# MCU.net
KiCad netlist of a schematic drawn in EAGLE
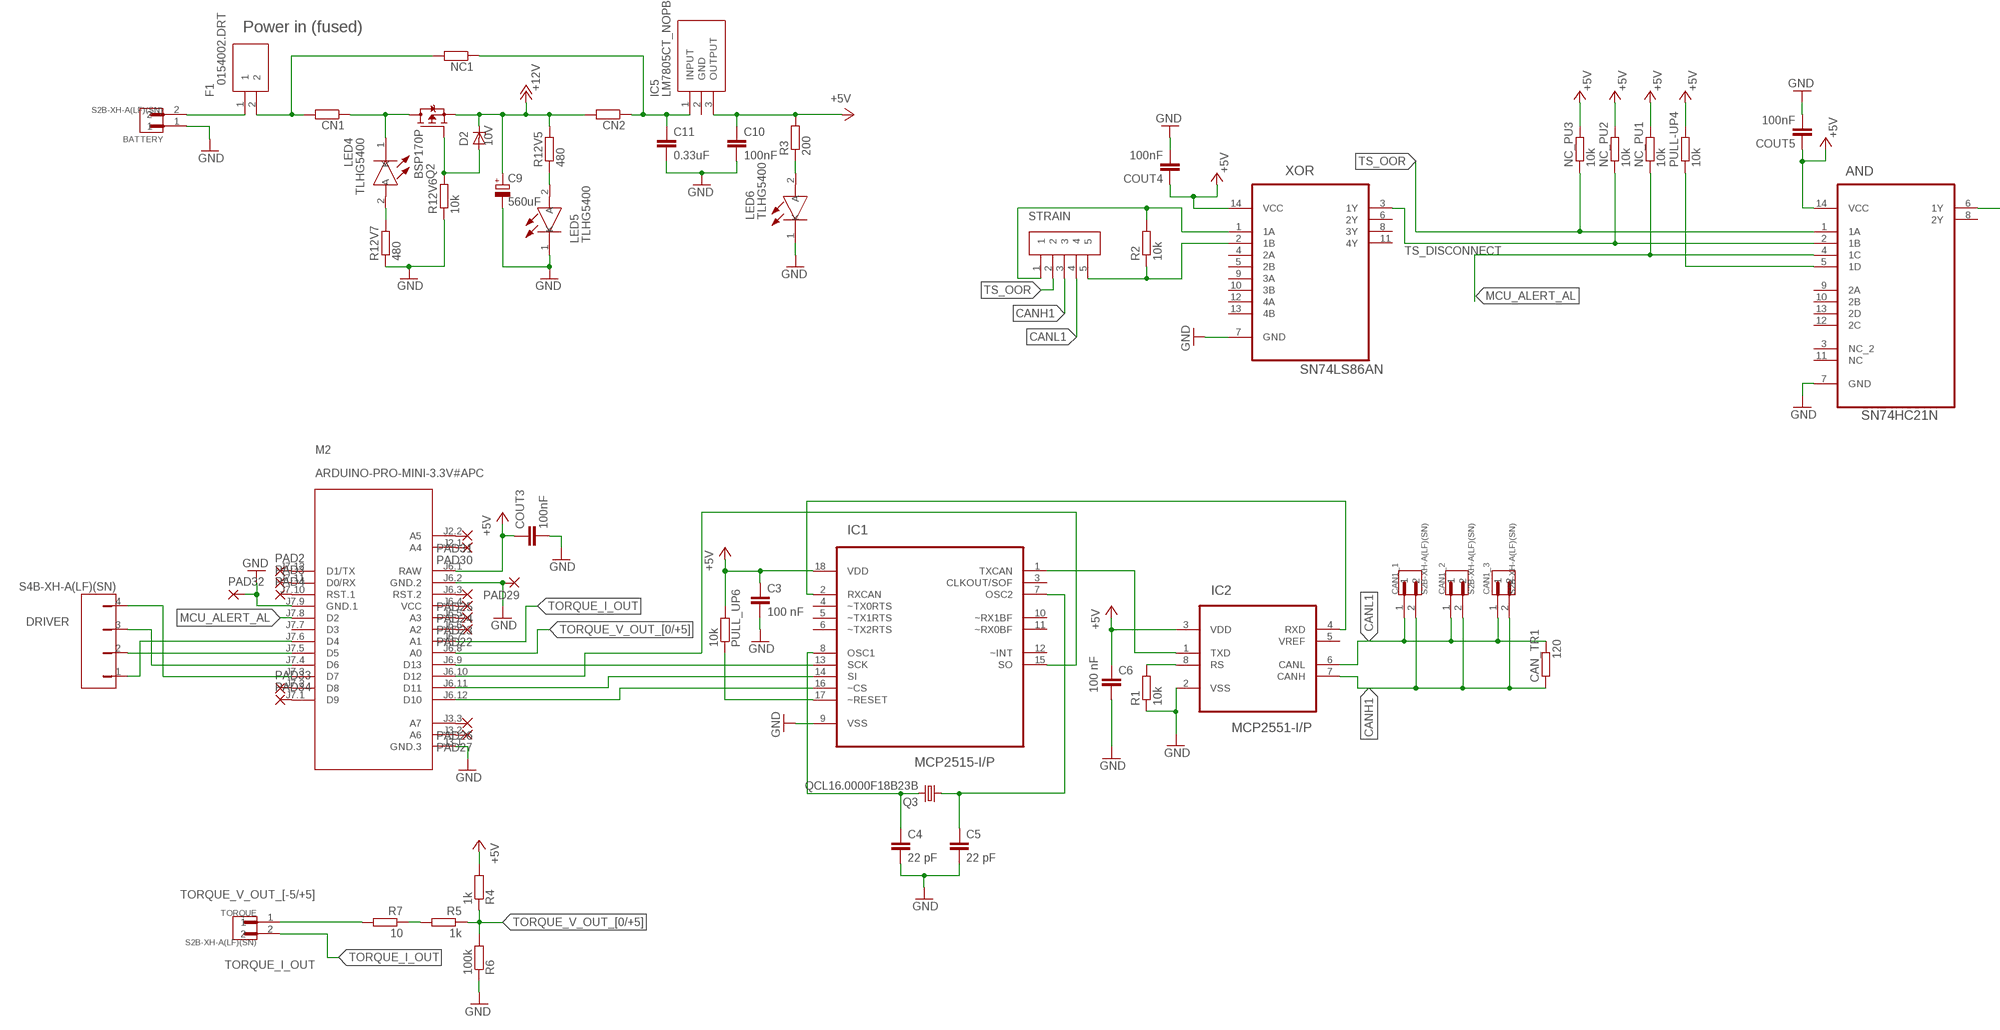
[diagram p0: schematic, sheet 1, part 1 of 2]
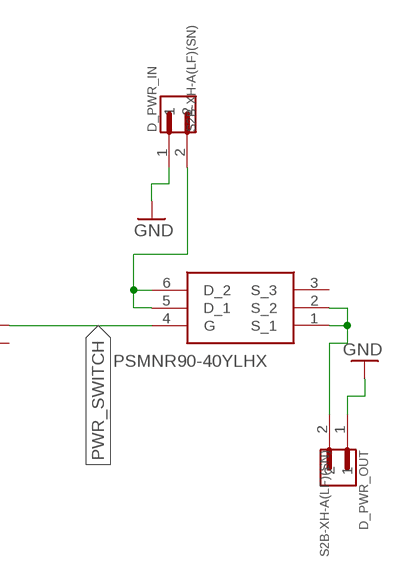
[diagram p1: schematic, sheet 1, part 2 of 2]
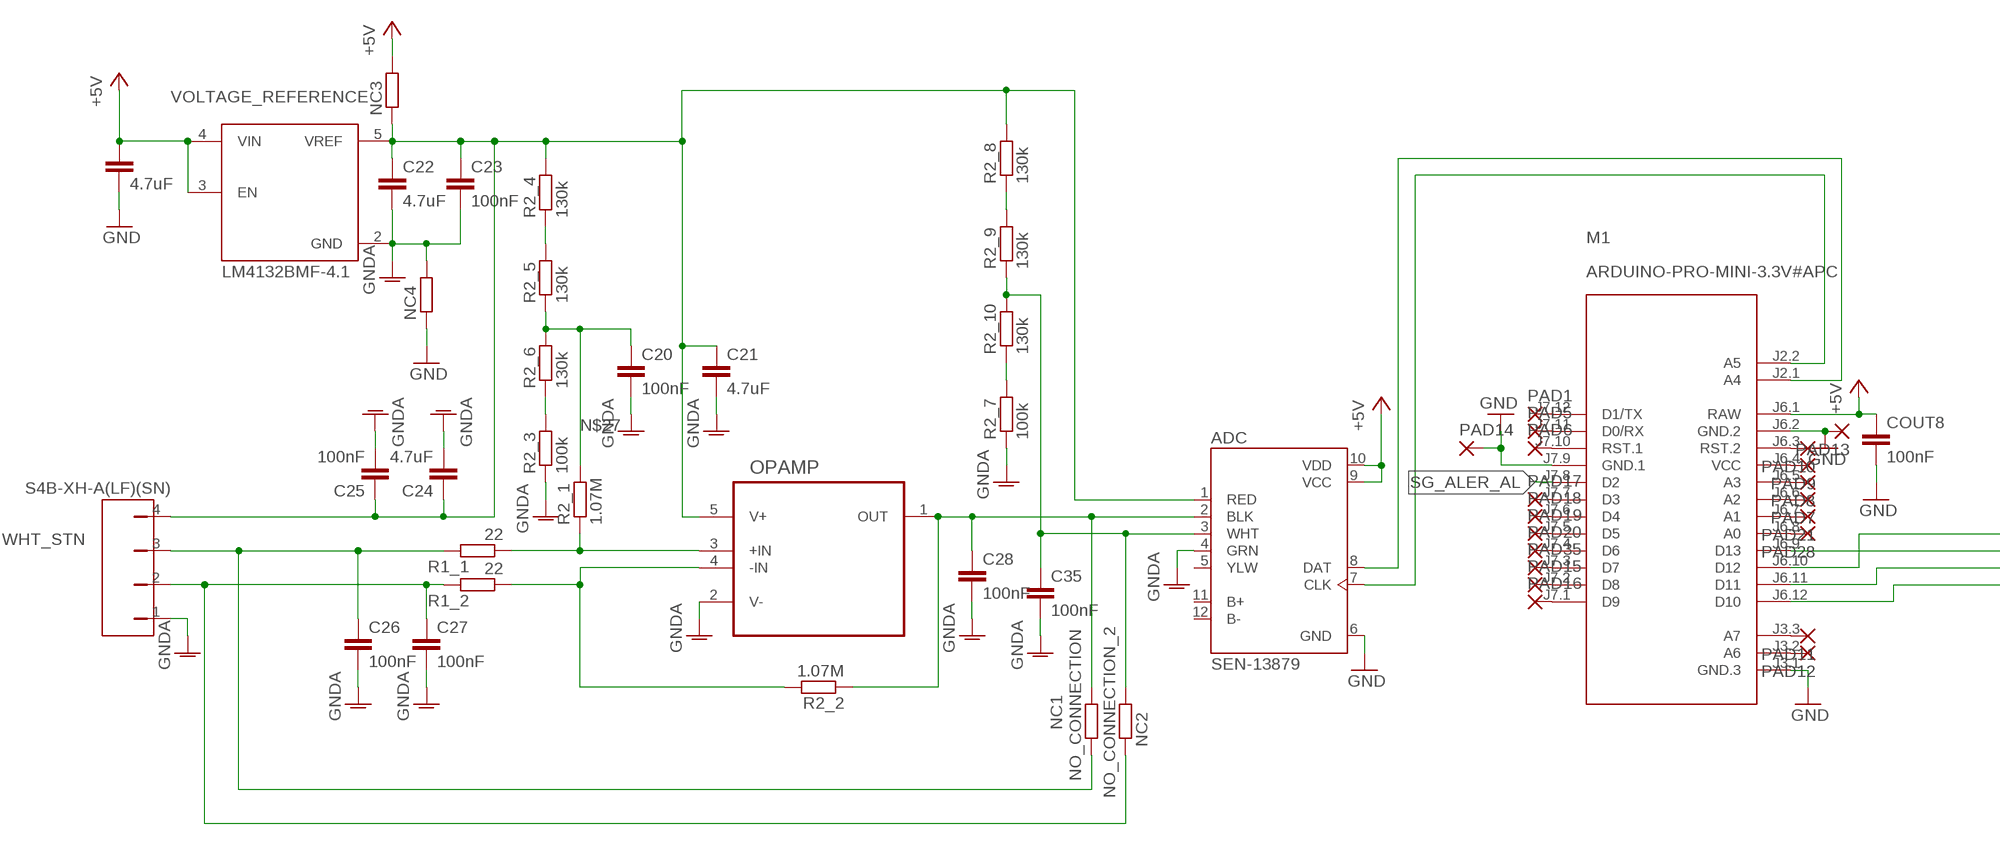
[diagram p2: schematic, sheet 2, part 1 of 2]
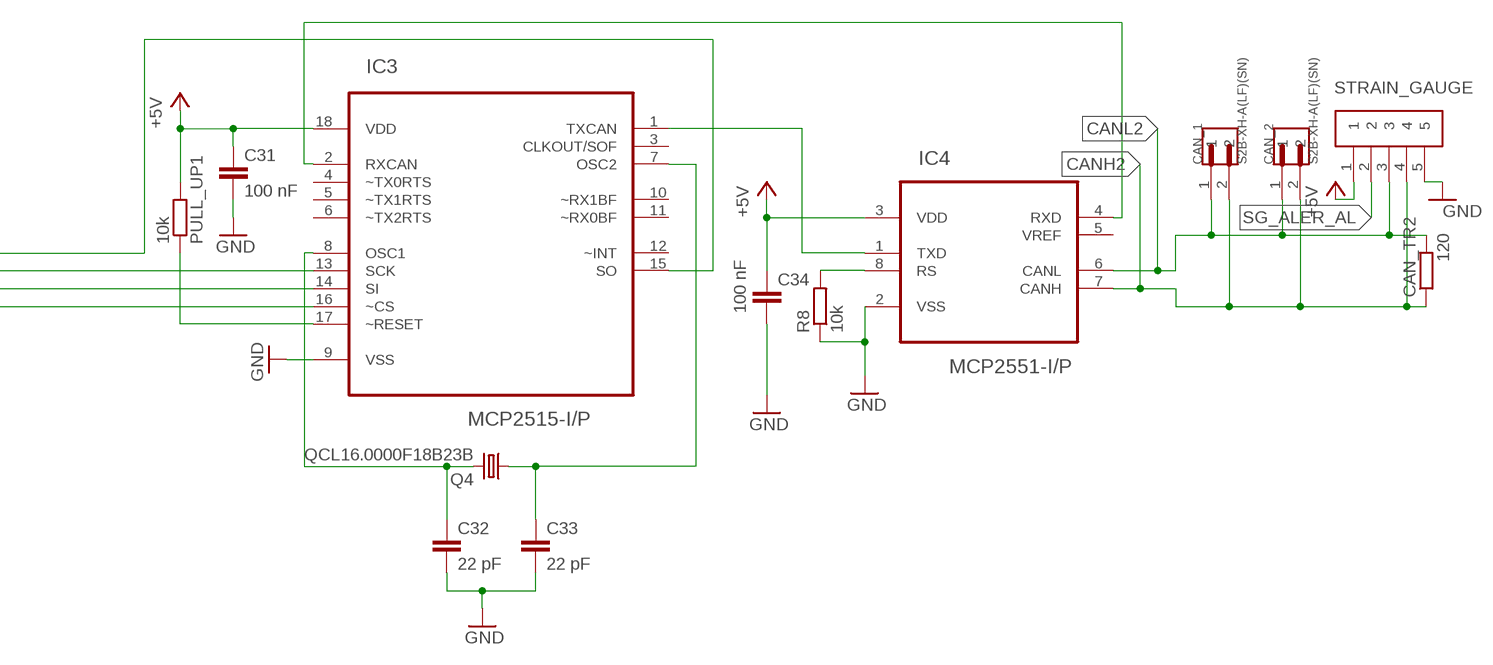
[diagram p3: schematic, sheet 2, part 2 of 2]

(export (version "E")
  (design (tool "Eeschema 10.0.6"))
  (components
    (comp (ref "ADC")
      (value "SEN-13879")
      (footprint "eagle-import:SPARKFUN_SEN-13879")
      (fields (field (name "DIGI-KEY_PART_NUMBER") "1568-1436-ND") (field (name "MF") "SparkFun"))
      (libsource (lib "eagle-import") (part "SEN-13879"))
    )
    (comp (ref "C19")
      (value "4.7uF")
      (footprint "eagle-import:C0805")
      (libsource (lib "eagle-import") (part "C-EUC0805"))
    )
    (comp (ref "C20")
      (value "100nF")
      (footprint "eagle-import:C0805")
      (libsource (lib "eagle-import") (part "C-EUC0805"))
    )
    (comp (ref "C21")
      (value "4.7uF")
      (footprint "eagle-import:C0805")
      (libsource (lib "eagle-import") (part "C-EUC0805"))
    )
    (comp (ref "C22")
      (value "4.7uF")
      (footprint "eagle-import:C0805")
      (libsource (lib "eagle-import") (part "C-EUC0805"))
    )
    (comp (ref "C23")
      (value "100nF")
      (footprint "eagle-import:C0805")
      (libsource (lib "eagle-import") (part "C-EUC0805"))
    )
    (comp (ref "C24")
      (value "4.7uF")
      (footprint "eagle-import:C0805")
      (libsource (lib "eagle-import") (part "C-EUC0805"))
    )
    (comp (ref "C25")
      (value "100nF")
      (footprint "eagle-import:C0805")
      (libsource (lib "eagle-import") (part "C-EUC0805"))
    )
    (comp (ref "C26")
      (value "100nF")
      (footprint "eagle-import:C0805")
      (libsource (lib "eagle-import") (part "C-EUC0805"))
    )
    (comp (ref "C27")
      (value "100nF")
      (footprint "eagle-import:C0805")
      (libsource (lib "eagle-import") (part "C-EUC0805"))
    )
    (comp (ref "C28")
      (value "100nF")
      (footprint "eagle-import:C0805")
      (libsource (lib "eagle-import") (part "C-EUC0805"))
    )
    (comp (ref "C31")
      (value "100 nF")
      (footprint "eagle-import:C0805")
      (libsource (lib "eagle-import") (part "C-EUC0805"))
    )
    (comp (ref "C32")
      (value "22 pF")
      (footprint "eagle-import:C0805")
      (libsource (lib "eagle-import") (part "C-EUC0805"))
    )
    (comp (ref "C33")
      (value "22 pF")
      (footprint "eagle-import:C0805")
      (libsource (lib "eagle-import") (part "C-EUC0805"))
    )
    (comp (ref "C34")
      (value "100 nF")
      (footprint "eagle-import:C0805")
      (libsource (lib "eagle-import") (part "C-EUC0805"))
    )
    (comp (ref "C35")
      (value "100nF")
      (footprint "eagle-import:C0805")
      (libsource (lib "eagle-import") (part "C-EUC0805"))
    )
    (comp (ref "CAN_1")
      (value "S2B-XH-A(LF)(SN)")
      (footprint "eagle-import:JST_S2B-XH-A(LF)(SN)")
      (fields
        (field (name "DIGI-KEY_PART_NUMBER") "455-2257-ND")
        (field (name "MF") "JST Sales")
        (field (name "MP") "S2B-XH-A_LF__SN_")
      )
      (libsource (lib "eagle-import") (part "S2B-XH-A(LF)(SN)"))
    )
    (comp (ref "CAN_2")
      (value "S2B-XH-A(LF)(SN)")
      (footprint "eagle-import:JST_S2B-XH-A(LF)(SN)")
      (fields
        (field (name "DIGI-KEY_PART_NUMBER") "455-2257-ND")
        (field (name "MF") "JST Sales")
        (field (name "MP") "S2B-XH-A_LF__SN_")
      )
      (libsource (lib "eagle-import") (part "S2B-XH-A(LF)(SN)"))
    )
    (comp (ref "CAN_TR2")
      (value "120")
      (footprint "eagle-import:R0805")
      (libsource (lib "eagle-import") (part "R-EU_R0805"))
    )
    (comp (ref "COUT8")
      (value "100nF")
      (footprint "eagle-import:C0805")
      (libsource (lib "eagle-import") (part "C-EUC0805"))
    )
    (comp (ref "IC3")
      (value "MCP2515-I/P")
      (footprint "eagle-import:DIP254P762X432-18")
      (fields (field (name "MF") "Microchip"))
      (libsource (lib "eagle-import") (part "MCP2515-I/P"))
    )
    (comp (ref "IC4")
      (value "MCP2551-I/P")
      (footprint "eagle-import:DIP254P762X432-8")
      (fields (field (name "MF") "Microchip"))
      (libsource (lib "eagle-import") (part "MCP2551-I/P"))
    )
    (comp (ref "M1")
      (value "ARDUINO-PRO-MINI-3.3V#APC")
      (footprint "eagle-import:ARDUINO-PRO-MINI#APC")
      (libsource (lib "eagle-import") (part "ARDUINO-PRO-MINI-#APC3.3V"))
    )
    (comp (ref "NC3")
      (value "R-EU_R0805")
      (footprint "eagle-import:R0805")
      (libsource (lib "eagle-import") (part "R-EU_R0805"))
    )
    (comp (ref "NC4")
      (value "R-EU_R0805")
      (footprint "eagle-import:R0805")
      (libsource (lib "eagle-import") (part "R-EU_R0805"))
    )
    (comp (ref "NO_CONNECTION")
      (value "NC1")
      (footprint "eagle-import:R0805")
      (libsource (lib "eagle-import") (part "R-EU_R0805"))
    )
    (comp (ref "NO_CONNECTION_2")
      (value "NC2")
      (footprint "eagle-import:R0805")
      (libsource (lib "eagle-import") (part "R-EU_R0805"))
    )
    (comp (ref "OPAMP")
      (value "LMP7731MF")
      (footprint "eagle-import:SOT95P284X119-5N")
      (fields (field (name "MF") "Texas Instruments"))
      (libsource (lib "eagle-import") (part "LMP7731MF"))
    )
    (comp (ref "PAD1")
      (value "SMD2")
      (footprint "eagle-import:SMD1,27-2,54")
      (libsource (lib "eagle-import") (part "SMD2"))
    )
    (comp (ref "PAD5")
      (value "SMD2")
      (footprint "eagle-import:SMD1,27-2,54")
      (libsource (lib "eagle-import") (part "SMD2"))
    )
    (comp (ref "PAD6")
      (value "SMD2")
      (footprint "eagle-import:SMD1,27-2,54")
      (libsource (lib "eagle-import") (part "SMD2"))
    )
    (comp (ref "PAD7")
      (value "SMD2")
      (footprint "eagle-import:SMD1,27-2,54")
      (libsource (lib "eagle-import") (part "SMD2"))
    )
    (comp (ref "PAD8")
      (value "SMD2")
      (footprint "eagle-import:SMD1,27-2,54")
      (libsource (lib "eagle-import") (part "SMD2"))
    )
    (comp (ref "PAD9")
      (value "SMD2")
      (footprint "eagle-import:SMD1,27-2,54")
      (libsource (lib "eagle-import") (part "SMD2"))
    )
    (comp (ref "PAD10")
      (value "SMD2")
      (footprint "eagle-import:SMD1,27-2,54")
      (libsource (lib "eagle-import") (part "SMD2"))
    )
    (comp (ref "PAD11")
      (value "SMD2")
      (footprint "eagle-import:SMD1,27-2,54")
      (libsource (lib "eagle-import") (part "SMD2"))
    )
    (comp (ref "PAD12")
      (value "SMD2")
      (footprint "eagle-import:SMD1,27-2,54")
      (libsource (lib "eagle-import") (part "SMD2"))
    )
    (comp (ref "PAD13")
      (value "SMD2")
      (footprint "eagle-import:SMD1,27-2,54")
      (libsource (lib "eagle-import") (part "SMD2"))
    )
    (comp (ref "PAD14")
      (value "SMD2")
      (footprint "eagle-import:SMD1,27-2,54")
      (libsource (lib "eagle-import") (part "SMD2"))
    )
    (comp (ref "PAD15")
      (value "SMD2")
      (footprint "eagle-import:SMD1,27-2,54")
      (libsource (lib "eagle-import") (part "SMD2"))
    )
    (comp (ref "PAD16")
      (value "SMD2")
      (footprint "eagle-import:SMD1,27-2,54")
      (libsource (lib "eagle-import") (part "SMD2"))
    )
    (comp (ref "PAD17")
      (value "SMD2")
      (footprint "eagle-import:SMD1,27-2,54")
      (libsource (lib "eagle-import") (part "SMD2"))
    )
    (comp (ref "PAD18")
      (value "SMD2")
      (footprint "eagle-import:SMD1,27-2,54")
      (libsource (lib "eagle-import") (part "SMD2"))
    )
    (comp (ref "PAD19")
      (value "SMD2")
      (footprint "eagle-import:SMD1,27-2,54")
      (libsource (lib "eagle-import") (part "SMD2"))
    )
    (comp (ref "PAD20")
      (value "SMD2")
      (footprint "eagle-import:SMD1,27-2,54")
      (libsource (lib "eagle-import") (part "SMD2"))
    )
    (comp (ref "PAD21")
      (value "SMD2")
      (footprint "eagle-import:SMD1,27-2,54")
      (libsource (lib "eagle-import") (part "SMD2"))
    )
    (comp (ref "PAD28")
      (value "SMD2")
      (footprint "eagle-import:SMD1,27-2,54")
      (libsource (lib "eagle-import") (part "SMD2"))
    )
    (comp (ref "PAD35")
      (value "SMD2")
      (footprint "eagle-import:SMD1,27-2,54")
      (libsource (lib "eagle-import") (part "SMD2"))
    )
    (comp (ref "PULL_UP1")
      (value "10k")
      (footprint "eagle-import:R0805")
      (libsource (lib "eagle-import") (part "R-EU_R0805"))
    )
    (comp (ref "Q4")
      (value "QCL16.0000F18B23B")
      (footprint "eagle-import:HC49_S")
      (libsource (lib "eagle-import") (part "CRYSTALHC49S"))
    )
    (comp (ref "R1_1")
      (value "22")
      (footprint "eagle-import:R0805")
      (libsource (lib "eagle-import") (part "R-EU_R0805"))
    )
    (comp (ref "R1_2")
      (value "22")
      (footprint "eagle-import:R0805")
      (libsource (lib "eagle-import") (part "R-EU_R0805"))
    )
    (comp (ref "R2_1")
      (value "1.07M")
      (footprint "eagle-import:R0805")
      (libsource (lib "eagle-import") (part "R-EU_R0805"))
    )
    (comp (ref "R2_2")
      (value "1.07M")
      (footprint "eagle-import:R0805")
      (libsource (lib "eagle-import") (part "R-EU_R0805"))
    )
    (comp (ref "R2_3")
      (value "100k")
      (footprint "eagle-import:R0805")
      (libsource (lib "eagle-import") (part "R-EU_R0805"))
    )
    (comp (ref "R2_4")
      (value "130k")
      (footprint "eagle-import:R0805")
      (libsource (lib "eagle-import") (part "R-EU_R0805"))
    )
    (comp (ref "R2_5")
      (value "130k")
      (footprint "eagle-import:R0805")
      (libsource (lib "eagle-import") (part "R-EU_R0805"))
    )
    (comp (ref "R2_6")
      (value "130k")
      (footprint "eagle-import:R0805")
      (libsource (lib "eagle-import") (part "R-EU_R0805"))
    )
    (comp (ref "R2_7")
      (value "100k")
      (footprint "eagle-import:R0805")
      (libsource (lib "eagle-import") (part "R-EU_R0805"))
    )
    (comp (ref "R2_8")
      (value "130k")
      (footprint "eagle-import:R0805")
      (libsource (lib "eagle-import") (part "R-EU_R0805"))
    )
    (comp (ref "R2_9")
      (value "130k")
      (footprint "eagle-import:R0805")
      (libsource (lib "eagle-import") (part "R-EU_R0805"))
    )
    (comp (ref "R2_10")
      (value "130k")
      (footprint "eagle-import:R0805")
      (libsource (lib "eagle-import") (part "R-EU_R0805"))
    )
    (comp (ref "R8")
      (value "10k")
      (footprint "eagle-import:R0805")
      (libsource (lib "eagle-import") (part "R-EU_R0805"))
    )
    (comp (ref "STRAIN_GAUGE")
      (value "S5B-XH-A(LF)(SN)")
      (footprint "eagle-import:JST_S5B-XH-A(LF)(SN)")
      (fields (field (name "MF") "JST Sales") (field (name "MP") "S5B-XH-A_LF__SN_"))
      (libsource (lib "eagle-import") (part "S5B-XH-A(LF)(SN)"))
    )
    (comp (ref "VOLTAGE_REFERENCE")
      (value "LM4132BMF-4.1")
      (footprint "eagle-import:SOT95P280X145-5N")
      (fields (field (name "MF") "Texas Instruments"))
      (libsource (lib "eagle-import") (part "LM4132BMF-4.1"))
    )
    (comp (ref "WHT_STN")
      (value "S4B-XH-A(LF)(SN)")
      (footprint "eagle-import:S4B-XH-A(LF)(SN)")
      (fields (field (name "MF") "JST Sales") (field (name "MP") "S4B-XH-A_LF__SN_"))
      (libsource (lib "eagle-import") (part "S4B-XH-A(LF)(SN)"))
    )
    (comp (ref "AND")
      (value "SN74HC21N")
      (footprint "eagle-import:DIP254P762X508-14")
      (fields (field (name "MF") "Texas Instruments"))
      (libsource (lib "eagle-import") (part "SN74HC21N"))
    )
    (comp (ref "BATTERY")
      (value "S2B-XH-A(LF)(SN)")
      (footprint "eagle-import:JST_S2B-XH-A(LF)(SN)")
      (fields
        (field (name "DIGI-KEY_PART_NUMBER") "455-2257-ND")
        (field (name "MF") "JST Sales")
        (field (name "MP") "S2B-XH-A_LF__SN_")
      )
      (libsource (lib "eagle-import") (part "S2B-XH-A(LF)(SN)"))
    )
    (comp (ref "C3")
      (value "100 nF")
      (footprint "eagle-import:C0805")
      (libsource (lib "eagle-import") (part "C-EUC0805"))
    )
    (comp (ref "C4")
      (value "22 pF")
      (footprint "eagle-import:C0805")
      (libsource (lib "eagle-import") (part "C-EUC0805"))
    )
    (comp (ref "C5")
      (value "22 pF")
      (footprint "eagle-import:C0805")
      (libsource (lib "eagle-import") (part "C-EUC0805"))
    )
    (comp (ref "C6")
      (value "100 nF")
      (footprint "eagle-import:C0805")
      (libsource (lib "eagle-import") (part "C-EUC0805"))
    )
    (comp (ref "C9")
      (value "560uF")
      (footprint "eagle-import:PANASONIC_F")
      (libsource (lib "eagle-import") (part "CPOL-EUF"))
    )
    (comp (ref "C10")
      (value "100nF")
      (footprint "eagle-import:C0805")
      (libsource (lib "eagle-import") (part "C-EUC0805"))
    )
    (comp (ref "C11")
      (value "0.33uF")
      (footprint "eagle-import:C0805")
      (libsource (lib "eagle-import") (part "C-EUC0805"))
    )
    (comp (ref "CAN1_1")
      (value "S2B-XH-A(LF)(SN)")
      (footprint "eagle-import:JST_S2B-XH-A(LF)(SN)")
      (fields
        (field (name "DIGI-KEY_PART_NUMBER") "455-2257-ND")
        (field (name "MF") "JST Sales")
        (field (name "MP") "S2B-XH-A_LF__SN_")
      )
      (libsource (lib "eagle-import") (part "S2B-XH-A(LF)(SN)"))
    )
    (comp (ref "CAN1_2")
      (value "S2B-XH-A(LF)(SN)")
      (footprint "eagle-import:JST_S2B-XH-A(LF)(SN)")
      (fields
        (field (name "DIGI-KEY_PART_NUMBER") "455-2257-ND")
        (field (name "MF") "JST Sales")
        (field (name "MP") "S2B-XH-A_LF__SN_")
      )
      (libsource (lib "eagle-import") (part "S2B-XH-A(LF)(SN)"))
    )
    (comp (ref "CAN1_3")
      (value "S2B-XH-A(LF)(SN)")
      (footprint "eagle-import:JST_S2B-XH-A(LF)(SN)")
      (fields
        (field (name "DIGI-KEY_PART_NUMBER") "455-2257-ND")
        (field (name "MF") "JST Sales")
        (field (name "MP") "S2B-XH-A_LF__SN_")
      )
      (libsource (lib "eagle-import") (part "S2B-XH-A(LF)(SN)"))
    )
    (comp (ref "CAN_TR1")
      (value "120")
      (footprint "eagle-import:R0805")
      (libsource (lib "eagle-import") (part "R-EU_R0805"))
    )
    (comp (ref "CN1")
      (value "10k")
      (footprint "eagle-import:R0805")
      (libsource (lib "eagle-import") (part "R-EU_R0805"))
    )
    (comp (ref "CN2")
      (value "10k")
      (footprint "eagle-import:R0805")
      (libsource (lib "eagle-import") (part "R-EU_R0805"))
    )
    (comp (ref "COUT3")
      (value "100nF")
      (footprint "eagle-import:C0805")
      (libsource (lib "eagle-import") (part "C-EUC0805"))
    )
    (comp (ref "COUT4")
      (value "100nF")
      (footprint "eagle-import:C0805")
      (libsource (lib "eagle-import") (part "C-EUC0805"))
    )
    (comp (ref "COUT5")
      (value "100nF")
      (footprint "eagle-import:C0805")
      (libsource (lib "eagle-import") (part "C-EUC0805"))
    )
    (comp (ref "D2")
      (value "10V")
      (footprint "eagle-import:SMB")
      (libsource (lib "eagle-import") (part "ZENER-DIODESMB"))
    )
    (comp (ref "DRIVER")
      (value "S4B-XH-A(LF)(SN)")
      (footprint "eagle-import:S4B-XH-A(LF)(SN)")
      (fields (field (name "MF") "JST Sales") (field (name "MP") "S4B-XH-A_LF__SN_"))
      (libsource (lib "eagle-import") (part "S4B-XH-A(LF)(SN)"))
    )
    (comp (ref "D_PWR_IN")
      (value "S2B-XH-A(LF)(SN)")
      (footprint "eagle-import:JST_S2B-XH-A(LF)(SN)")
      (fields
        (field (name "DIGI-KEY_PART_NUMBER") "455-2257-ND")
        (field (name "MF") "JST Sales")
        (field (name "MP") "S2B-XH-A_LF__SN_")
      )
      (libsource (lib "eagle-import") (part "S2B-XH-A(LF)(SN)"))
    )
    (comp (ref "D_PWR_OUT")
      (value "S2B-XH-A(LF)(SN)")
      (footprint "eagle-import:JST_S2B-XH-A(LF)(SN)")
      (fields
        (field (name "DIGI-KEY_PART_NUMBER") "455-2257-ND")
        (field (name "MF") "JST Sales")
        (field (name "MP") "S2B-XH-A_LF__SN_")
      )
      (libsource (lib "eagle-import") (part "S2B-XH-A(LF)(SN)"))
    )
    (comp (ref "F1")
      (value "0154002.DRT")
      (footprint "eagle-import:FUSM9750X381N")
      (fields (field (name "MOUSER_PART_NUMBER") "576-0154002.DRT"))
      (libsource (lib "eagle-import") (part "0154002.DRT"))
    )
    (comp (ref "IC1")
      (value "MCP2515-I/P")
      (footprint "eagle-import:DIP254P762X432-18")
      (fields (field (name "MF") "Microchip"))
      (libsource (lib "eagle-import") (part "MCP2515-I/P"))
    )
    (comp (ref "IC2")
      (value "MCP2551-I/P")
      (footprint "eagle-import:DIP254P762X432-8")
      (fields (field (name "MF") "Microchip"))
      (libsource (lib "eagle-import") (part "MCP2551-I/P"))
    )
    (comp (ref "IC5")
      (value "LM7805CT_NOPB")
      (footprint "eagle-import:TO254P470X1028X1955-3P")
      (fields
        (field (name "MANUFACTURER_PART_NUMBER") "LM7805CT/NOPB")
        (field (name "MOUSER_PART_NUMBER") "926-LM7805CT/NOPB")
      )
      (libsource (lib "eagle-import") (part "LM7805CT_NOPB"))
    )
    (comp (ref "LED4")
      (value "TLHG5400")
      (footprint "eagle-import:TLHG5400")
      (fields (field (name "MOUSER_PART_NUMBER") "78-TLHG5400"))
      (libsource (lib "eagle-import") (part "TLHG5400"))
    )
    (comp (ref "LED5")
      (value "TLHG5400")
      (footprint "eagle-import:TLHG5400")
      (fields (field (name "MOUSER_PART_NUMBER") "78-TLHG5400"))
      (libsource (lib "eagle-import") (part "TLHG5400"))
    )
    (comp (ref "LED6")
      (value "TLHG5400")
      (footprint "eagle-import:TLHG5400")
      (fields (field (name "MOUSER_PART_NUMBER") "78-TLHG5400"))
      (libsource (lib "eagle-import") (part "TLHG5400"))
    )
    (comp (ref "M2")
      (value "ARDUINO-PRO-MINI-3.3V#APC")
      (footprint "eagle-import:ARDUINO-PRO-MINI#APC")
      (libsource (lib "eagle-import") (part "ARDUINO-PRO-MINI-#APC3.3V"))
    )
    (comp (ref "NC1")
      (value "10k")
      (footprint "eagle-import:R0805")
      (libsource (lib "eagle-import") (part "R-EU_R0805"))
    )
    (comp (ref "NC_PU1")
      (value "10k")
      (footprint "eagle-import:R0805")
      (libsource (lib "eagle-import") (part "R-EU_R0805"))
    )
    (comp (ref "NC_PU2")
      (value "10k")
      (footprint "eagle-import:R0805")
      (libsource (lib "eagle-import") (part "R-EU_R0805"))
    )
    (comp (ref "NC_PU3")
      (value "10k")
      (footprint "eagle-import:R0805")
      (libsource (lib "eagle-import") (part "R-EU_R0805"))
    )
    (comp (ref "PAD2")
      (value "SMD2")
      (footprint "eagle-import:SMD1,27-2,54")
      (libsource (lib "eagle-import") (part "SMD2"))
    )
    (comp (ref "PAD3")
      (value "SMD2")
      (footprint "eagle-import:SMD1,27-2,54")
      (libsource (lib "eagle-import") (part "SMD2"))
    )
    (comp (ref "PAD4")
      (value "SMD2")
      (footprint "eagle-import:SMD1,27-2,54")
      (libsource (lib "eagle-import") (part "SMD2"))
    )
    (comp (ref "PAD22")
      (value "SMD2")
      (footprint "eagle-import:SMD1,27-2,54")
      (libsource (lib "eagle-import") (part "SMD2"))
    )
    (comp (ref "PAD23")
      (value "SMD2")
      (footprint "eagle-import:SMD1,27-2,54")
      (libsource (lib "eagle-import") (part "SMD2"))
    )
    (comp (ref "PAD24")
      (value "SMD2")
      (footprint "eagle-import:SMD1,27-2,54")
      (libsource (lib "eagle-import") (part "SMD2"))
    )
    (comp (ref "PAD25")
      (value "SMD2")
      (footprint "eagle-import:SMD1,27-2,54")
      (libsource (lib "eagle-import") (part "SMD2"))
    )
    (comp (ref "PAD26")
      (value "SMD2")
      (footprint "eagle-import:SMD1,27-2,54")
      (libsource (lib "eagle-import") (part "SMD2"))
    )
    (comp (ref "PAD27")
      (value "SMD2")
      (footprint "eagle-import:SMD1,27-2,54")
      (libsource (lib "eagle-import") (part "SMD2"))
    )
    (comp (ref "PAD29")
      (value "SMD2")
      (footprint "eagle-import:SMD1,27-2,54")
      (libsource (lib "eagle-import") (part "SMD2"))
    )
    (comp (ref "PAD30")
      (value "SMD2")
      (footprint "eagle-import:SMD1,27-2,54")
      (libsource (lib "eagle-import") (part "SMD2"))
    )
    (comp (ref "PAD31")
      (value "SMD2")
      (footprint "eagle-import:SMD1,27-2,54")
      (libsource (lib "eagle-import") (part "SMD2"))
    )
    (comp (ref "PAD32")
      (value "SMD2")
      (footprint "eagle-import:SMD1,27-2,54")
      (libsource (lib "eagle-import") (part "SMD2"))
    )
    (comp (ref "PAD33")
      (value "SMD2")
      (footprint "eagle-import:SMD1,27-2,54")
      (libsource (lib "eagle-import") (part "SMD2"))
    )
    (comp (ref "PAD34")
      (value "SMD2")
      (footprint "eagle-import:SMD1,27-2,54")
      (libsource (lib "eagle-import") (part "SMD2"))
    )
    (comp (ref "PULL-UP4")
      (value "10k")
      (footprint "eagle-import:R0805")
      (libsource (lib "eagle-import") (part "R-EU_R0805"))
    )
    (comp (ref "PULL_UP6")
      (value "10k")
      (footprint "eagle-import:R0805")
      (libsource (lib "eagle-import") (part "R-EU_R0805"))
    )
    (comp (ref "Q1")
      (value "PSMNR90-40YLHX")
      (footprint "eagle-import:PSMNR9040YLHX")
      (fields (field (name "MOUSER_PART_NUMBER") "771-PSMNR90-40YLHX"))
      (libsource (lib "eagle-import") (part "PSMNR90-40YLHX"))
    )
    (comp (ref "Q2")
      (value "BSP170P")
      (footprint "eagle-import:SOT223")
      (libsource (lib "eagle-import") (part "BSP170P"))
    )
    (comp (ref "Q3")
      (value "QCL16.0000F18B23B")
      (footprint "eagle-import:HC49_S")
      (libsource (lib "eagle-import") (part "CRYSTALHC49S"))
    )
    (comp (ref "R1")
      (value "10k")
      (footprint "eagle-import:R0805")
      (libsource (lib "eagle-import") (part "R-EU_R0805"))
    )
    (comp (ref "R2")
      (value "10k")
      (footprint "eagle-import:R0805")
      (libsource (lib "eagle-import") (part "R-EU_R0805"))
    )
    (comp (ref "R3")
      (value "200")
      (footprint "eagle-import:R0805")
      (libsource (lib "eagle-import") (part "R-EU_R0805"))
    )
    (comp (ref "R4")
      (value "1k")
      (footprint "eagle-import:R0805")
      (libsource (lib "eagle-import") (part "R-EU_R0805"))
    )
    (comp (ref "R5")
      (value "1k")
      (footprint "eagle-import:R0805")
      (libsource (lib "eagle-import") (part "R-EU_R0805"))
    )
    (comp (ref "R6")
      (value "100k")
      (footprint "eagle-import:R0805")
      (libsource (lib "eagle-import") (part "R-EU_R0805"))
    )
    (comp (ref "R7")
      (value "10")
      (footprint "eagle-import:R0805")
      (libsource (lib "eagle-import") (part "R-EU_R0805"))
    )
    (comp (ref "R12V5")
      (value "480")
      (footprint "eagle-import:R0805")
      (libsource (lib "eagle-import") (part "R-EU_R0805"))
    )
    (comp (ref "R12V6")
      (value "10k")
      (footprint "eagle-import:R0805")
      (libsource (lib "eagle-import") (part "R-EU_R0805"))
    )
    (comp (ref "R12V7")
      (value "480")
      (footprint "eagle-import:R0805")
      (libsource (lib "eagle-import") (part "R-EU_R0805"))
    )
    (comp (ref "STRAIN")
      (value "S5B-XH-A(LF)(SN)")
      (footprint "eagle-import:JST_S5B-XH-A(LF)(SN)")
      (fields (field (name "MF") "JST Sales") (field (name "MP") "S5B-XH-A_LF__SN_"))
      (libsource (lib "eagle-import") (part "S5B-XH-A(LF)(SN)"))
    )
    (comp (ref "TORQUE")
      (value "S2B-XH-A(LF)(SN)")
      (footprint "eagle-import:JST_S2B-XH-A(LF)(SN)")
      (fields
        (field (name "DIGI-KEY_PART_NUMBER") "455-2257-ND")
        (field (name "MF") "JST Sales")
        (field (name "MP") "S2B-XH-A_LF__SN_")
      )
      (libsource (lib "eagle-import") (part "S2B-XH-A(LF)(SN)"))
    )
    (comp (ref "XOR")
      (value "SN74LS86AN")
      (footprint "eagle-import:DIP254P762X508-14")
      (fields (field (name "MF") "Texas Instruments"))
      (libsource (lib "eagle-import") (part "SN74LS86AN"))
    )
  )
  (nets
    (net (code "1") (name "+5V") (class "Default")
      (node (ref "ADC") (pin "10") (pinfunction "VDD_10") (pintype "power_in"))
      (node (ref "ADC") (pin "9") (pinfunction "VCC_9") (pintype "power_in"))
      (node (ref "AND") (pin "14") (pinfunction "VCC_14") (pintype "power_in"))
      (node (ref "C10") (pin "1") (pinfunction "1_1") (pintype "passive"))
      (node (ref "C19") (pin "1") (pinfunction "1_1") (pintype "passive"))
      (node (ref "C3") (pin "1") (pinfunction "1_1") (pintype "passive"))
      (node (ref "C31") (pin "1") (pinfunction "1_1") (pintype "passive"))
      (node (ref "C34") (pin "1") (pinfunction "1_1") (pintype "passive"))
      (node (ref "C6") (pin "1") (pinfunction "1_1") (pintype "passive"))
      (node (ref "COUT3") (pin "1") (pinfunction "1_1") (pintype "passive"))
      (node (ref "COUT4") (pin "1") (pinfunction "1_1") (pintype "passive"))
      (node (ref "COUT5") (pin "1") (pinfunction "1_1") (pintype "passive"))
      (node (ref "COUT8") (pin "1") (pinfunction "1_1") (pintype "passive"))
      (node (ref "IC1") (pin "18") (pinfunction "VDD_18") (pintype "power_in"))
      (node (ref "IC2") (pin "3") (pinfunction "VDD_3") (pintype "power_in"))
      (node (ref "IC3") (pin "18") (pinfunction "VDD_18") (pintype "power_in"))
      (node (ref "IC4") (pin "3") (pinfunction "VDD_3") (pintype "power_in"))
      (node (ref "IC5") (pin "3") (pinfunction "OUTPUT_3") (pintype "bidirectional"))
      (node (ref "M1") (pin "J6.1") (pinfunction "RAW_J6.1") (pintype "power_in"))
      (node (ref "M2") (pin "J6.1") (pinfunction "RAW_J6.1") (pintype "power_in"))
      (node (ref "NC3") (pin "2") (pinfunction "2_2") (pintype "passive"))
      (node (ref "NC_PU1") (pin "2") (pinfunction "2_2") (pintype "passive"))
      (node (ref "NC_PU2") (pin "2") (pinfunction "2_2") (pintype "passive"))
      (node (ref "NC_PU3") (pin "2") (pinfunction "2_2") (pintype "passive"))
      (node (ref "PULL-UP4") (pin "2") (pinfunction "2_2") (pintype "passive"))
      (node (ref "PULL_UP1") (pin "2") (pinfunction "2_2") (pintype "passive"))
      (node (ref "PULL_UP6") (pin "2") (pinfunction "2_2") (pintype "passive"))
      (node (ref "R3") (pin "2") (pinfunction "2_2") (pintype "passive"))
      (node (ref "R4") (pin "2") (pinfunction "2_2") (pintype "passive"))
      (node (ref "STRAIN_GAUGE") (pin "1") (pinfunction "1_1") (pintype "passive"))
      (node (ref "VOLTAGE_REFERENCE") (pin "3") (pinfunction "EN_3") (pintype "input"))
      (node (ref "VOLTAGE_REFERENCE") (pin "4") (pinfunction "VIN_4") (pintype "power_in"))
      (node (ref "XOR") (pin "14") (pinfunction "VCC_14") (pintype "power_in"))
    )
    (net (code "2") (name "+12V") (class "Default")
      (node (ref "C9") (pin "+") (pinfunction "+_+") (pintype "passive"))
      (node (ref "CN2") (pin "2") (pinfunction "2_2") (pintype "passive"))
      (node (ref "D2") (pin "C") (pinfunction "C_C") (pintype "passive"))
      (node (ref "Q2") (pin "3") (pinfunction "S_3") (pintype "passive"))
      (node (ref "R12V5") (pin "2") (pinfunction "2_2") (pintype "passive"))
    )
    (net (code "3") (name "CANH1") (class "Default")
      (node (ref "CAN1_1") (pin "2") (pinfunction "2_2") (pintype "passive"))
      (node (ref "CAN1_2") (pin "2") (pinfunction "2_2") (pintype "passive"))
      (node (ref "CAN1_3") (pin "2") (pinfunction "2_2") (pintype "passive"))
      (node (ref "CAN_TR1") (pin "1") (pinfunction "1_1") (pintype "passive"))
      (node (ref "IC2") (pin "7") (pinfunction "CANH_7") (pintype "bidirectional"))
      (node (ref "STRAIN") (pin "3") (pinfunction "3_3") (pintype "passive"))
    )
    (net (code "4") (name "CANH2") (class "Default")
      (node (ref "CAN_1") (pin "2") (pinfunction "2_2") (pintype "passive"))
      (node (ref "CAN_2") (pin "2") (pinfunction "2_2") (pintype "passive"))
      (node (ref "CAN_TR2") (pin "1") (pinfunction "1_1") (pintype "passive"))
      (node (ref "IC4") (pin "7") (pinfunction "CANH_7") (pintype "bidirectional"))
      (node (ref "STRAIN_GAUGE") (pin "4") (pinfunction "4_4") (pintype "passive"))
    )
    (net (code "5") (name "CANL1") (class "Default")
      (node (ref "CAN1_1") (pin "1") (pinfunction "1_1") (pintype "passive"))
      (node (ref "CAN1_2") (pin "1") (pinfunction "1_1") (pintype "passive"))
      (node (ref "CAN1_3") (pin "1") (pinfunction "1_1") (pintype "passive"))
      (node (ref "CAN_TR1") (pin "2") (pinfunction "2_2") (pintype "passive"))
      (node (ref "IC2") (pin "6") (pinfunction "CANL_6") (pintype "bidirectional"))
      (node (ref "STRAIN") (pin "4") (pinfunction "4_4") (pintype "passive"))
    )
    (net (code "6") (name "CANL2") (class "Default")
      (node (ref "CAN_1") (pin "1") (pinfunction "1_1") (pintype "passive"))
      (node (ref "CAN_2") (pin "1") (pinfunction "1_1") (pintype "passive"))
      (node (ref "CAN_TR2") (pin "2") (pinfunction "2_2") (pintype "passive"))
      (node (ref "IC4") (pin "6") (pinfunction "CANL_6") (pintype "bidirectional"))
      (node (ref "STRAIN_GAUGE") (pin "3") (pinfunction "3_3") (pintype "passive"))
    )
    (net (code "7") (name "GND") (class "Default")
      (node (ref "ADC") (pin "6") (pinfunction "GND_6") (pintype "power_in"))
      (node (ref "AND") (pin "7") (pinfunction "GND_7") (pintype "passive"))
      (node (ref "BATTERY") (pin "1") (pinfunction "1_1") (pintype "passive"))
      (node (ref "C10") (pin "2") (pinfunction "2_2") (pintype "passive"))
      (node (ref "C11") (pin "2") (pinfunction "2_2") (pintype "passive"))
      (node (ref "C19") (pin "2") (pinfunction "2_2") (pintype "passive"))
      (node (ref "C3") (pin "2") (pinfunction "2_2") (pintype "passive"))
      (node (ref "C31") (pin "2") (pinfunction "2_2") (pintype "passive"))
      (node (ref "C32") (pin "2") (pinfunction "2_2") (pintype "passive"))
      (node (ref "C33") (pin "2") (pinfunction "2_2") (pintype "passive"))
      (node (ref "C34") (pin "2") (pinfunction "2_2") (pintype "passive"))
      (node (ref "C4") (pin "2") (pinfunction "2_2") (pintype "passive"))
      (node (ref "C5") (pin "2") (pinfunction "2_2") (pintype "passive"))
      (node (ref "C6") (pin "2") (pinfunction "2_2") (pintype "passive"))
      (node (ref "C9") (pin "-") (pinfunction "-_-") (pintype "passive"))
      (node (ref "COUT3") (pin "2") (pinfunction "2_2") (pintype "passive"))
      (node (ref "COUT4") (pin "2") (pinfunction "2_2") (pintype "passive"))
      (node (ref "COUT5") (pin "2") (pinfunction "2_2") (pintype "passive"))
      (node (ref "COUT8") (pin "2") (pinfunction "2_2") (pintype "passive"))
      (node (ref "D_PWR_IN") (pin "1") (pinfunction "1_1") (pintype "passive"))
      (node (ref "D_PWR_OUT") (pin "1") (pinfunction "1_1") (pintype "passive"))
      (node (ref "IC1") (pin "9") (pinfunction "VSS_9") (pintype "power_in"))
      (node (ref "IC2") (pin "2") (pinfunction "VSS_2") (pintype "power_in"))
      (node (ref "IC3") (pin "9") (pinfunction "VSS_9") (pintype "power_in"))
      (node (ref "IC4") (pin "2") (pinfunction "VSS_2") (pintype "power_in"))
      (node (ref "LED5") (pin "1") (pinfunction "K_1") (pintype "bidirectional"))
      (node (ref "LED6") (pin "1") (pinfunction "K_1") (pintype "bidirectional"))
      (node (ref "M1") (pin "J3.1") (pinfunction "GND.3_J3.1") (pintype "bidirectional"))
      (node (ref "M1") (pin "J6.2") (pinfunction "GND.2_J6.2") (pintype "power_in"))
      (node (ref "M1") (pin "J7.9") (pinfunction "GND.1_J7.9") (pintype "power_in"))
      (node (ref "M2") (pin "J3.1") (pinfunction "GND.3_J3.1") (pintype "bidirectional"))
      (node (ref "M2") (pin "J6.2") (pinfunction "GND.2_J6.2") (pintype "power_in"))
      (node (ref "M2") (pin "J7.9") (pinfunction "GND.1_J7.9") (pintype "power_in"))
      (node (ref "NC4") (pin "1") (pinfunction "1_1") (pintype "passive"))
      (node (ref "PAD13") (pin "1") (pinfunction "P_1") (pintype "passive"))
      (node (ref "PAD14") (pin "1") (pinfunction "P_1") (pintype "passive"))
      (node (ref "PAD29") (pin "1") (pinfunction "P_1") (pintype "passive"))
      (node (ref "PAD32") (pin "1") (pinfunction "P_1") (pintype "passive"))
      (node (ref "R1") (pin "1") (pinfunction "1_1") (pintype "passive"))
      (node (ref "R12V6") (pin "1") (pinfunction "1_1") (pintype "passive"))
      (node (ref "R12V7") (pin "1") (pinfunction "1_1") (pintype "passive"))
      (node (ref "R6") (pin "1") (pinfunction "1_1") (pintype "passive"))
      (node (ref "R8") (pin "1") (pinfunction "1_1") (pintype "passive"))
      (node (ref "STRAIN_GAUGE") (pin "5") (pinfunction "5_5") (pintype "passive"))
      (node (ref "XOR") (pin "7") (pinfunction "GND_7") (pintype "passive"))
    )
    (net (code "8") (name "GNDA") (class "Default")
      (node (ref "ADC") (pin "4") (pinfunction "GRN_4") (pintype "input"))
      (node (ref "C20") (pin "2") (pinfunction "2_2") (pintype "passive"))
      (node (ref "C21") (pin "2") (pinfunction "2_2") (pintype "passive"))
      (node (ref "C22") (pin "2") (pinfunction "2_2") (pintype "passive"))
      (node (ref "C23") (pin "2") (pinfunction "2_2") (pintype "passive"))
      (node (ref "C24") (pin "2") (pinfunction "2_2") (pintype "passive"))
      (node (ref "C25") (pin "2") (pinfunction "2_2") (pintype "passive"))
      (node (ref "C26") (pin "2") (pinfunction "2_2") (pintype "passive"))
      (node (ref "C27") (pin "2") (pinfunction "2_2") (pintype "passive"))
      (node (ref "C28") (pin "2") (pinfunction "2_2") (pintype "passive"))
      (node (ref "C35") (pin "2") (pinfunction "2_2") (pintype "passive"))
      (node (ref "NC4") (pin "2") (pinfunction "2_2") (pintype "passive"))
      (node (ref "OPAMP") (pin "2") (pinfunction "V-_2") (pintype "power_in"))
      (node (ref "R2_3") (pin "1") (pinfunction "1_1") (pintype "passive"))
      (node (ref "R2_7") (pin "1") (pinfunction "1_1") (pintype "passive"))
      (node (ref "VOLTAGE_REFERENCE") (pin "2") (pinfunction "GND_2") (pintype "power_in"))
      (node (ref "WHT_STN") (pin "1") (pinfunction "1_1") (pintype "passive"))
    )
    (net (code "9") (name "MCU_ALERT_AL") (class "Default")
      (node (ref "AND") (pin "4") (pinfunction "1C_4") (pintype "input"))
      (node (ref "M2") (pin "J7.8") (pinfunction "D2_J7.8") (pintype "bidirectional"))
      (node (ref "NC_PU1") (pin "1") (pinfunction "1_1") (pintype "passive"))
    )
    (net (code "10") (name "N$27") (class "Default")
      (node (ref "C20") (pin "1") (pinfunction "1_1") (pintype "passive"))
      (node (ref "R2_1") (pin "2") (pinfunction "2_2") (pintype "passive"))
      (node (ref "R2_5") (pin "1") (pinfunction "1_1") (pintype "passive"))
      (node (ref "R2_6") (pin "2") (pinfunction "2_2") (pintype "passive"))
    )
    (net (code "11") (name "Net-(ADC-BLK)") (class "Default")
      (node (ref "ADC") (pin "2") (pinfunction "BLK_2") (pintype "bidirectional"))
      (node (ref "C28") (pin "1") (pinfunction "1_1") (pintype "passive"))
      (node (ref "NO_CONNECTION") (pin "2") (pinfunction "2_2") (pintype "passive"))
      (node (ref "OPAMP") (pin "1") (pinfunction "OUT_1") (pintype "output"))
      (node (ref "R2_2") (pin "1") (pinfunction "1_1") (pintype "passive"))
    )
    (net (code "12") (name "Net-(ADC-CLK)") (class "Default")
      (node (ref "ADC") (pin "7") (pinfunction "CLK_7") (pintype "input"))
      (node (ref "M1") (pin "J2.2") (pinfunction "A5_J2.2") (pintype "bidirectional"))
    )
    (net (code "13") (name "Net-(ADC-DAT)") (class "Default")
      (node (ref "ADC") (pin "8") (pinfunction "DAT_8") (pintype "output"))
      (node (ref "M1") (pin "J2.1") (pinfunction "A4_J2.1") (pintype "bidirectional"))
    )
    (net (code "14") (name "Net-(ADC-RED)") (class "Default")
      (node (ref "ADC") (pin "1") (pinfunction "RED_1") (pintype "bidirectional"))
      (node (ref "C21") (pin "1") (pinfunction "1_1") (pintype "passive"))
      (node (ref "C22") (pin "1") (pinfunction "1_1") (pintype "passive"))
      (node (ref "C23") (pin "1") (pinfunction "1_1") (pintype "passive"))
      (node (ref "C24") (pin "1") (pinfunction "1_1") (pintype "passive"))
      (node (ref "C25") (pin "1") (pinfunction "1_1") (pintype "passive"))
      (node (ref "NC3") (pin "1") (pinfunction "1_1") (pintype "passive"))
      (node (ref "OPAMP") (pin "5") (pinfunction "V+_5") (pintype "power_in"))
      (node (ref "R2_4") (pin "2") (pinfunction "2_2") (pintype "passive"))
      (node (ref "R2_8") (pin "2") (pinfunction "2_2") (pintype "passive"))
      (node (ref "VOLTAGE_REFERENCE") (pin "5") (pinfunction "VREF_5") (pintype "power_in"))
      (node (ref "WHT_STN") (pin "4") (pinfunction "4_4") (pintype "passive"))
    )
    (net (code "15") (name "Net-(ADC-WHT)") (class "Default")
      (node (ref "ADC") (pin "3") (pinfunction "WHT_3") (pintype "input"))
      (node (ref "C35") (pin "1") (pinfunction "1_1") (pintype "passive"))
      (node (ref "NO_CONNECTION_2") (pin "2") (pinfunction "2_2") (pintype "passive"))
      (node (ref "R2_10") (pin "2") (pinfunction "2_2") (pintype "passive"))
      (node (ref "R2_9") (pin "1") (pinfunction "1_1") (pintype "passive"))
    )
    (net (code "16") (name "Net-(AND-1D)") (class "Default")
      (node (ref "AND") (pin "5") (pinfunction "1D_5") (pintype "input"))
      (node (ref "PULL-UP4") (pin "1") (pinfunction "1_1") (pintype "passive"))
    )
    (net (code "17") (name "Net-(BATTERY-Pad2)") (class "Default")
      (node (ref "BATTERY") (pin "2") (pinfunction "2_2") (pintype "passive"))
      (node (ref "F1") (pin "1") (pinfunction "1_1") (pintype "bidirectional"))
    )
    (net (code "18") (name "Net-(C26-Pad1)") (class "Default")
      (node (ref "C26") (pin "1") (pinfunction "1_1") (pintype "passive"))
      (node (ref "NO_CONNECTION") (pin "1") (pinfunction "1_1") (pintype "passive"))
      (node (ref "R1_1") (pin "2") (pinfunction "2_2") (pintype "passive"))
      (node (ref "WHT_STN") (pin "3") (pinfunction "3_3") (pintype "passive"))
    )
    (net (code "19") (name "Net-(C27-Pad1)") (class "Default")
      (node (ref "C27") (pin "1") (pinfunction "1_1") (pintype "passive"))
      (node (ref "NO_CONNECTION_2") (pin "1") (pinfunction "1_1") (pintype "passive"))
      (node (ref "R1_2") (pin "2") (pinfunction "2_2") (pintype "passive"))
      (node (ref "WHT_STN") (pin "2") (pinfunction "2_2") (pintype "passive"))
    )
    (net (code "20") (name "Net-(CN1-Pad2)") (class "Default")
      (node (ref "CN1") (pin "2") (pinfunction "2_2") (pintype "passive"))
      (node (ref "F1") (pin "2") (pinfunction "2_2") (pintype "bidirectional"))
      (node (ref "NC1") (pin "2") (pinfunction "2_2") (pintype "passive"))
    )
    (net (code "21") (name "Net-(IC1-OSC1)") (class "Default")
      (node (ref "C4") (pin "1") (pinfunction "1_1") (pintype "passive"))
      (node (ref "IC1") (pin "8") (pinfunction "OSC1_8") (pintype "input"))
      (node (ref "Q3") (pin "2") (pinfunction "2_2") (pintype "passive"))
    )
    (net (code "22") (name "Net-(IC1-OSC2)") (class "Default")
      (node (ref "C5") (pin "1") (pinfunction "1_1") (pintype "passive"))
      (node (ref "IC1") (pin "7") (pinfunction "OSC2_7") (pintype "output"))
      (node (ref "Q3") (pin "1") (pinfunction "1_1") (pintype "passive"))
    )
    (net (code "23") (name "Net-(IC1-RXCAN)") (class "Default")
      (node (ref "IC1") (pin "2") (pinfunction "RXCAN_2") (pintype "input"))
      (node (ref "IC2") (pin "4") (pinfunction "RXD_4") (pintype "output"))
    )
    (net (code "24") (name "Net-(IC1-SCK)") (class "Default")
      (node (ref "IC1") (pin "13") (pinfunction "SCK_13") (pintype "input"))
      (node (ref "M2") (pin "J6.9") (pinfunction "D13_J6.9") (pintype "bidirectional"))
    )
    (net (code "25") (name "Net-(IC1-SI)") (class "Default")
      (node (ref "IC1") (pin "14") (pinfunction "SI_14") (pintype "input"))
      (node (ref "M2") (pin "J6.11") (pinfunction "D11_J6.11") (pintype "bidirectional"))
    )
    (net (code "26") (name "Net-(IC1-SO)") (class "Default")
      (node (ref "IC1") (pin "15") (pinfunction "SO_15") (pintype "output"))
      (node (ref "M2") (pin "J6.10") (pinfunction "D12_J6.10") (pintype "bidirectional"))
    )
    (net (code "27") (name "Net-(IC1-TXCAN)") (class "Default")
      (node (ref "IC1") (pin "1") (pinfunction "TXCAN_1") (pintype "output"))
      (node (ref "IC2") (pin "1") (pinfunction "TXD_1") (pintype "input"))
    )
    (net (code "28") (name "Net-(IC1-~{CS})") (class "Default")
      (node (ref "IC1") (pin "16") (pinfunction "~{CS}_16") (pintype "input"))
      (node (ref "M2") (pin "J6.12") (pinfunction "D10_J6.12") (pintype "bidirectional"))
    )
    (net (code "29") (name "Net-(IC1-~{RESET})") (class "Default")
      (node (ref "IC1") (pin "17") (pinfunction "~{RESET}_17") (pintype "input"))
      (node (ref "PULL_UP6") (pin "1") (pinfunction "1_1") (pintype "passive"))
    )
    (net (code "30") (name "Net-(IC2-RS)") (class "Default")
      (node (ref "IC2") (pin "8") (pinfunction "RS_8") (pintype "input"))
      (node (ref "R1") (pin "2") (pinfunction "2_2") (pintype "passive"))
    )
    (net (code "31") (name "Net-(IC3-OSC1)") (class "Default")
      (node (ref "C32") (pin "1") (pinfunction "1_1") (pintype "passive"))
      (node (ref "IC3") (pin "8") (pinfunction "OSC1_8") (pintype "input"))
      (node (ref "Q4") (pin "2") (pinfunction "2_2") (pintype "passive"))
    )
    (net (code "32") (name "Net-(IC3-OSC2)") (class "Default")
      (node (ref "C33") (pin "1") (pinfunction "1_1") (pintype "passive"))
      (node (ref "IC3") (pin "7") (pinfunction "OSC2_7") (pintype "output"))
      (node (ref "Q4") (pin "1") (pinfunction "1_1") (pintype "passive"))
    )
    (net (code "33") (name "Net-(IC3-RXCAN)") (class "Default")
      (node (ref "IC3") (pin "2") (pinfunction "RXCAN_2") (pintype "input"))
      (node (ref "IC4") (pin "4") (pinfunction "RXD_4") (pintype "output"))
    )
    (net (code "34") (name "Net-(IC3-SCK)") (class "Default")
      (node (ref "IC3") (pin "13") (pinfunction "SCK_13") (pintype "input"))
      (node (ref "M1") (pin "J6.9") (pinfunction "D13_J6.9") (pintype "bidirectional"))
    )
    (net (code "35") (name "Net-(IC3-SI)") (class "Default")
      (node (ref "IC3") (pin "14") (pinfunction "SI_14") (pintype "input"))
      (node (ref "M1") (pin "J6.11") (pinfunction "D11_J6.11") (pintype "bidirectional"))
    )
    (net (code "36") (name "Net-(IC3-SO)") (class "Default")
      (node (ref "IC3") (pin "15") (pinfunction "SO_15") (pintype "output"))
      (node (ref "M1") (pin "J6.10") (pinfunction "D12_J6.10") (pintype "bidirectional"))
    )
    (net (code "37") (name "Net-(IC3-TXCAN)") (class "Default")
      (node (ref "IC3") (pin "1") (pinfunction "TXCAN_1") (pintype "output"))
      (node (ref "IC4") (pin "1") (pinfunction "TXD_1") (pintype "input"))
    )
    (net (code "38") (name "Net-(IC3-~{CS})") (class "Default")
      (node (ref "IC3") (pin "16") (pinfunction "~{CS}_16") (pintype "input"))
      (node (ref "M1") (pin "J6.12") (pinfunction "D10_J6.12") (pintype "bidirectional"))
    )
    (net (code "39") (name "Net-(IC3-~{RESET})") (class "Default")
      (node (ref "IC3") (pin "17") (pinfunction "~{RESET}_17") (pintype "input"))
      (node (ref "PULL_UP1") (pin "1") (pinfunction "1_1") (pintype "passive"))
    )
    (net (code "40") (name "Net-(IC4-RS)") (class "Default")
      (node (ref "IC4") (pin "8") (pinfunction "RS_8") (pintype "input"))
      (node (ref "R8") (pin "2") (pinfunction "2_2") (pintype "passive"))
    )
    (net (code "41") (name "Net-(IC5-INPUT)") (class "Default")
      (node (ref "C11") (pin "1") (pinfunction "1_1") (pintype "passive"))
      (node (ref "CN2") (pin "1") (pinfunction "1_1") (pintype "passive"))
      (node (ref "IC5") (pin "1") (pinfunction "INPUT_1") (pintype "bidirectional"))
      (node (ref "NC1") (pin "1") (pinfunction "1_1") (pintype "passive"))
    )
    (net (code "42") (name "Net-(LED4-A)") (class "Default")
      (node (ref "LED4") (pin "2") (pinfunction "A_2") (pintype "bidirectional"))
      (node (ref "R12V7") (pin "2") (pinfunction "2_2") (pintype "passive"))
    )
    (net (code "43") (name "Net-(LED4-K)") (class "Default")
      (node (ref "CN1") (pin "1") (pinfunction "1_1") (pintype "passive"))
      (node (ref "LED4") (pin "1") (pinfunction "K_1") (pintype "bidirectional"))
      (node (ref "Q2") (pin "2") (pinfunction "D_2") (pintype "passive"))
      (node (ref "Q2") (pin "4") (pinfunction "D_4") (pintype "passive"))
    )
    (net (code "44") (name "Net-(LED5-A)") (class "Default")
      (node (ref "LED5") (pin "2") (pinfunction "A_2") (pintype "bidirectional"))
      (node (ref "R12V5") (pin "1") (pinfunction "1_1") (pintype "passive"))
    )
    (net (code "45") (name "Net-(LED6-A)") (class "Default")
      (node (ref "LED6") (pin "2") (pinfunction "A_2") (pintype "bidirectional"))
      (node (ref "R3") (pin "1") (pinfunction "1_1") (pintype "passive"))
    )
    (net (code "46") (name "Net-(M1-A0)") (class "Default")
      (node (ref "M1") (pin "J6.8") (pinfunction "A0_J6.8") (pintype "bidirectional"))
      (node (ref "PAD28") (pin "1") (pinfunction "P_1") (pintype "passive"))
    )
    (net (code "47") (name "Net-(M1-A1)") (class "Default")
      (node (ref "M1") (pin "J6.7") (pinfunction "A1_J6.7") (pintype "bidirectional"))
      (node (ref "PAD21") (pin "1") (pinfunction "P_1") (pintype "passive"))
    )
    (net (code "48") (name "Net-(M1-A2)") (class "Default")
      (node (ref "M1") (pin "J6.6") (pinfunction "A2_J6.6") (pintype "bidirectional"))
      (node (ref "PAD7") (pin "1") (pinfunction "P_1") (pintype "passive"))
    )
    (net (code "49") (name "Net-(M1-A3)") (class "Default")
      (node (ref "M1") (pin "J6.5") (pinfunction "A3_J6.5") (pintype "bidirectional"))
      (node (ref "PAD8") (pin "1") (pinfunction "P_1") (pintype "passive"))
    )
    (net (code "50") (name "Net-(M1-A6)") (class "Default")
      (node (ref "M1") (pin "J3.2") (pinfunction "A6_J3.2") (pintype "bidirectional"))
      (node (ref "PAD12") (pin "1") (pinfunction "P_1") (pintype "passive"))
    )
    (net (code "51") (name "Net-(M1-A7)") (class "Default")
      (node (ref "M1") (pin "J3.3") (pinfunction "A7_J3.3") (pintype "bidirectional"))
      (node (ref "PAD11") (pin "1") (pinfunction "P_1") (pintype "passive"))
    )
    (net (code "52") (name "Net-(M1-D0{slash}RX)") (class "Default")
      (node (ref "M1") (pin "J7.11") (pinfunction "D0/RX_J7.11") (pintype "bidirectional"))
      (node (ref "PAD5") (pin "1") (pinfunction "P_1") (pintype "passive"))
    )
    (net (code "53") (name "Net-(M1-D1{slash}TX)") (class "Default")
      (node (ref "M1") (pin "J7.12") (pinfunction "D1/TX_J7.12") (pintype "bidirectional"))
      (node (ref "PAD1") (pin "1") (pinfunction "P_1") (pintype "passive"))
    )
    (net (code "54") (name "Net-(M1-D3)") (class "Default")
      (node (ref "M1") (pin "J7.7") (pinfunction "D3_J7.7") (pintype "bidirectional"))
      (node (ref "PAD17") (pin "1") (pinfunction "P_1") (pintype "passive"))
    )
    (net (code "55") (name "Net-(M1-D4)") (class "Default")
      (node (ref "M1") (pin "J7.6") (pinfunction "D4_J7.6") (pintype "bidirectional"))
      (node (ref "PAD18") (pin "1") (pinfunction "P_1") (pintype "passive"))
    )
    (net (code "56") (name "Net-(M1-D5)") (class "Default")
      (node (ref "M1") (pin "J7.5") (pinfunction "D5_J7.5") (pintype "bidirectional"))
      (node (ref "PAD19") (pin "1") (pinfunction "P_1") (pintype "passive"))
    )
    (net (code "57") (name "Net-(M1-D6)") (class "Default")
      (node (ref "M1") (pin "J7.4") (pinfunction "D6_J7.4") (pintype "bidirectional"))
      (node (ref "PAD20") (pin "1") (pinfunction "P_1") (pintype "passive"))
    )
    (net (code "58") (name "Net-(M1-D7)") (class "Default")
      (node (ref "M1") (pin "J7.3") (pinfunction "D7_J7.3") (pintype "bidirectional"))
      (node (ref "PAD35") (pin "1") (pinfunction "P_1") (pintype "passive"))
    )
    (net (code "59") (name "Net-(M1-D8)") (class "Default")
      (node (ref "M1") (pin "J7.2") (pinfunction "D8_J7.2") (pintype "bidirectional"))
      (node (ref "PAD15") (pin "1") (pinfunction "P_1") (pintype "passive"))
    )
    (net (code "60") (name "Net-(M1-D9)") (class "Default")
      (node (ref "M1") (pin "J7.1") (pinfunction "D9_J7.1") (pintype "bidirectional"))
      (node (ref "PAD16") (pin "1") (pinfunction "P_1") (pintype "passive"))
    )
    (net (code "61") (name "Net-(M1-RST.1)") (class "Default")
      (node (ref "M1") (pin "J7.10") (pinfunction "RST.1_J7.10") (pintype "bidirectional"))
      (node (ref "PAD6") (pin "1") (pinfunction "P_1") (pintype "passive"))
    )
    (net (code "62") (name "Net-(M1-RST.2)") (class "Default")
      (node (ref "M1") (pin "J6.3") (pinfunction "RST.2_J6.3") (pintype "bidirectional"))
      (node (ref "PAD10") (pin "1") (pinfunction "P_1") (pintype "passive"))
    )
    (net (code "63") (name "Net-(M1-VCC)") (class "Default")
      (node (ref "M1") (pin "J6.4") (pinfunction "VCC_J6.4") (pintype "power_in"))
      (node (ref "PAD9") (pin "1") (pinfunction "P_1") (pintype "passive"))
    )
    (net (code "64") (name "Net-(M2-A2)") (class "Default")
      (node (ref "M2") (pin "J6.6") (pinfunction "A2_J6.6") (pintype "bidirectional"))
      (node (ref "PAD22") (pin "1") (pinfunction "P_1") (pintype "passive"))
    )
    (net (code "65") (name "Net-(M2-A3)") (class "Default")
      (node (ref "M2") (pin "J6.5") (pinfunction "A3_J6.5") (pintype "bidirectional"))
      (node (ref "PAD23") (pin "1") (pinfunction "P_1") (pintype "passive"))
    )
    (net (code "66") (name "Net-(M2-A4)") (class "Default")
      (node (ref "M2") (pin "J2.1") (pinfunction "A4_J2.1") (pintype "bidirectional"))
      (node (ref "PAD30") (pin "1") (pinfunction "P_1") (pintype "passive"))
    )
    (net (code "67") (name "Net-(M2-A5)") (class "Default")
      (node (ref "M2") (pin "J2.2") (pinfunction "A5_J2.2") (pintype "bidirectional"))
      (node (ref "PAD31") (pin "1") (pinfunction "P_1") (pintype "passive"))
    )
    (net (code "68") (name "Net-(M2-A6)") (class "Default")
      (node (ref "M2") (pin "J3.2") (pinfunction "A6_J3.2") (pintype "bidirectional"))
      (node (ref "PAD27") (pin "1") (pinfunction "P_1") (pintype "passive"))
    )
    (net (code "69") (name "Net-(M2-A7)") (class "Default")
      (node (ref "M2") (pin "J3.3") (pinfunction "A7_J3.3") (pintype "bidirectional"))
      (node (ref "PAD26") (pin "1") (pinfunction "P_1") (pintype "passive"))
    )
    (net (code "70") (name "Net-(M2-D0{slash}RX)") (class "Default")
      (node (ref "M2") (pin "J7.11") (pinfunction "D0/RX_J7.11") (pintype "bidirectional"))
      (node (ref "PAD3") (pin "1") (pinfunction "P_1") (pintype "passive"))
    )
    (net (code "71") (name "Net-(M2-D1{slash}TX)") (class "Default")
      (node (ref "M2") (pin "J7.12") (pinfunction "D1/TX_J7.12") (pintype "bidirectional"))
      (node (ref "PAD2") (pin "1") (pinfunction "P_1") (pintype "passive"))
    )
    (net (code "72") (name "Net-(M2-D4)") (class "Default")
      (node (ref "DRIVER") (pin "1") (pinfunction "1_1") (pintype "passive"))
      (node (ref "M2") (pin "J7.6") (pinfunction "D4_J7.6") (pintype "bidirectional"))
    )
    (net (code "73") (name "Net-(M2-D5)") (class "Default")
      (node (ref "DRIVER") (pin "2") (pinfunction "2_2") (pintype "passive"))
      (node (ref "M2") (pin "J7.5") (pinfunction "D5_J7.5") (pintype "bidirectional"))
    )
    (net (code "74") (name "Net-(M2-D6)") (class "Default")
      (node (ref "DRIVER") (pin "3") (pinfunction "3_3") (pintype "passive"))
      (node (ref "M2") (pin "J7.4") (pinfunction "D6_J7.4") (pintype "bidirectional"))
    )
    (net (code "75") (name "Net-(M2-D7)") (class "Default")
      (node (ref "DRIVER") (pin "4") (pinfunction "4_4") (pintype "passive"))
      (node (ref "M2") (pin "J7.3") (pinfunction "D7_J7.3") (pintype "bidirectional"))
    )
    (net (code "76") (name "Net-(M2-D8)") (class "Default")
      (node (ref "M2") (pin "J7.2") (pinfunction "D8_J7.2") (pintype "bidirectional"))
      (node (ref "PAD33") (pin "1") (pinfunction "P_1") (pintype "passive"))
    )
    (net (code "77") (name "Net-(M2-D9)") (class "Default")
      (node (ref "M2") (pin "J7.1") (pinfunction "D9_J7.1") (pintype "bidirectional"))
      (node (ref "PAD34") (pin "1") (pinfunction "P_1") (pintype "passive"))
    )
    (net (code "78") (name "Net-(M2-RST.1)") (class "Default")
      (node (ref "M2") (pin "J7.10") (pinfunction "RST.1_J7.10") (pintype "bidirectional"))
      (node (ref "PAD4") (pin "1") (pinfunction "P_1") (pintype "passive"))
    )
    (net (code "79") (name "Net-(M2-RST.2)") (class "Default")
      (node (ref "M2") (pin "J6.3") (pinfunction "RST.2_J6.3") (pintype "bidirectional"))
      (node (ref "PAD25") (pin "1") (pinfunction "P_1") (pintype "passive"))
    )
    (net (code "80") (name "Net-(M2-VCC)") (class "Default")
      (node (ref "M2") (pin "J6.4") (pinfunction "VCC_J6.4") (pintype "power_in"))
      (node (ref "PAD24") (pin "1") (pinfunction "P_1") (pintype "passive"))
    )
    (net (code "81") (name "Net-(OPAMP-+IN)") (class "Default")
      (node (ref "OPAMP") (pin "3") (pinfunction "+IN_3") (pintype "input"))
      (node (ref "R1_1") (pin "1") (pinfunction "1_1") (pintype "passive"))
      (node (ref "R2_1") (pin "1") (pinfunction "1_1") (pintype "passive"))
    )
    (net (code "82") (name "Net-(OPAMP--IN)") (class "Default")
      (node (ref "OPAMP") (pin "4") (pinfunction "-IN_4") (pintype "input"))
      (node (ref "R1_2") (pin "1") (pinfunction "1_1") (pintype "passive"))
      (node (ref "R2_2") (pin "2") (pinfunction "2_2") (pintype "passive"))
    )
    (net (code "83") (name "Net-(Q1-D_1)") (class "Default")
      (node (ref "D_PWR_IN") (pin "2") (pinfunction "2_2") (pintype "passive"))
      (node (ref "Q1") (pin "5") (pinfunction "D_1_5") (pintype "bidirectional"))
      (node (ref "Q1") (pin "6") (pinfunction "D_2_6") (pintype "bidirectional"))
    )
    (net (code "84") (name "Net-(Q1-S_1)") (class "Default")
      (node (ref "D_PWR_OUT") (pin "2") (pinfunction "2_2") (pintype "passive"))
      (node (ref "Q1") (pin "1") (pinfunction "S_1_1") (pintype "bidirectional"))
      (node (ref "Q1") (pin "2") (pinfunction "S_2_2") (pintype "bidirectional"))
    )
    (net (code "85") (name "Net-(Q2-G)") (class "Default")
      (node (ref "D2") (pin "A") (pinfunction "A_A") (pintype "passive"))
      (node (ref "Q2") (pin "1") (pinfunction "G_1") (pintype "passive"))
      (node (ref "R12V6") (pin "2") (pinfunction "2_2") (pintype "passive"))
    )
    (net (code "86") (name "Net-(R2_3-Pad2)") (class "Default")
      (node (ref "R2_3") (pin "2") (pinfunction "2_2") (pintype "passive"))
      (node (ref "R2_6") (pin "1") (pinfunction "1_1") (pintype "passive"))
    )
    (net (code "87") (name "Net-(R2_4-Pad1)") (class "Default")
      (node (ref "R2_4") (pin "1") (pinfunction "1_1") (pintype "passive"))
      (node (ref "R2_5") (pin "2") (pinfunction "2_2") (pintype "passive"))
    )
    (net (code "88") (name "Net-(R2_8-Pad1)") (class "Default")
      (node (ref "R2_8") (pin "1") (pinfunction "1_1") (pintype "passive"))
      (node (ref "R2_9") (pin "2") (pinfunction "2_2") (pintype "passive"))
    )
    (net (code "89") (name "Net-(R2_10-Pad1)") (class "Default")
      (node (ref "R2_10") (pin "1") (pinfunction "1_1") (pintype "passive"))
      (node (ref "R2_7") (pin "2") (pinfunction "2_2") (pintype "passive"))
    )
    (net (code "90") (name "Net-(R5-Pad2)") (class "Default")
      (node (ref "R5") (pin "2") (pinfunction "2_2") (pintype "passive"))
      (node (ref "R7") (pin "1") (pinfunction "1_1") (pintype "passive"))
    )
    (net (code "91") (name "Net-(XOR-1A)") (class "Default")
      (node (ref "R2") (pin "2") (pinfunction "2_2") (pintype "passive"))
      (node (ref "STRAIN") (pin "1") (pinfunction "1_1") (pintype "passive"))
      (node (ref "XOR") (pin "1") (pinfunction "1A_1") (pintype "input"))
    )
    (net (code "92") (name "Net-(XOR-1B)") (class "Default")
      (node (ref "R2") (pin "1") (pinfunction "1_1") (pintype "passive"))
      (node (ref "STRAIN") (pin "5") (pinfunction "5_5") (pintype "passive"))
      (node (ref "XOR") (pin "2") (pinfunction "1B_2") (pintype "input"))
    )
    (net (code "93") (name "PWR_SWITCH") (class "Default")
      (node (ref "AND") (pin "6") (pinfunction "1Y_6") (pintype "output"))
      (node (ref "Q1") (pin "4") (pinfunction "G_4") (pintype "bidirectional"))
    )
    (net (code "94") (name "SG_ALER_AL") (class "Default")
      (node (ref "M1") (pin "J7.8") (pinfunction "D2_J7.8") (pintype "bidirectional"))
      (node (ref "STRAIN_GAUGE") (pin "2") (pinfunction "2_2") (pintype "passive"))
    )
    (net (code "95") (name "TORQUE_I_OUT") (class "Default")
      (node (ref "M2") (pin "J6.7") (pinfunction "A1_J6.7") (pintype "bidirectional"))
      (node (ref "TORQUE") (pin "2") (pinfunction "2_2") (pintype "passive"))
    )
    (net (code "96") (name "TORQUE_V_OUT_[-5{slash}+5]") (class "Default")
      (node (ref "R7") (pin "2") (pinfunction "2_2") (pintype "passive"))
      (node (ref "TORQUE") (pin "1") (pinfunction "1_1") (pintype "passive"))
    )
    (net (code "97") (name "TORQUE_V_OUT_[0{slash}+5]") (class "Default")
      (node (ref "M2") (pin "J6.8") (pinfunction "A0_J6.8") (pintype "bidirectional"))
      (node (ref "R4") (pin "1") (pinfunction "1_1") (pintype "passive"))
      (node (ref "R5") (pin "1") (pinfunction "1_1") (pintype "passive"))
      (node (ref "R6") (pin "2") (pinfunction "2_2") (pintype "passive"))
    )
    (net (code "98") (name "TS_DISCONNECT") (class "Default")
      (node (ref "AND") (pin "2") (pinfunction "1B_2") (pintype "input"))
      (node (ref "NC_PU2") (pin "1") (pinfunction "1_1") (pintype "passive"))
      (node (ref "XOR") (pin "3") (pinfunction "1Y_3") (pintype "output"))
    )
    (net (code "99") (name "TS_OOR") (class "Default")
      (node (ref "AND") (pin "1") (pinfunction "1A_1") (pintype "input"))
      (node (ref "NC_PU3") (pin "1") (pinfunction "1_1") (pintype "passive"))
      (node (ref "STRAIN") (pin "2") (pinfunction "2_2") (pintype "passive"))
    )
    (net (code "100") (name "unconnected-(ADC-B+-Pad11)") (class "Default")
      (node (ref "ADC") (pin "11") (pinfunction "B+_11") (pintype "input"))
    )
    (net (code "101") (name "unconnected-(ADC-B--Pad12)") (class "Default")
      (node (ref "ADC") (pin "12") (pinfunction "B-_12") (pintype "input"))
    )
    (net (code "102") (name "unconnected-(ADC-YLW-Pad5)") (class "Default")
      (node (ref "ADC") (pin "5") (pinfunction "YLW_5") (pintype "bidirectional"))
    )
    (net (code "103") (name "unconnected-(AND-2A-Pad9)") (class "Default")
      (node (ref "AND") (pin "9") (pinfunction "2A_9") (pintype "input"))
    )
    (net (code "104") (name "unconnected-(AND-2B-Pad10)") (class "Default")
      (node (ref "AND") (pin "10") (pinfunction "2B_10") (pintype "input"))
    )
    (net (code "105") (name "unconnected-(AND-2C-Pad12)") (class "Default")
      (node (ref "AND") (pin "12") (pinfunction "2C_12") (pintype "input"))
    )
    (net (code "106") (name "unconnected-(AND-2D-Pad13)") (class "Default")
      (node (ref "AND") (pin "13") (pinfunction "2D_13") (pintype "input"))
    )
    (net (code "107") (name "unconnected-(AND-2Y-Pad8)") (class "Default")
      (node (ref "AND") (pin "8") (pinfunction "2Y_8") (pintype "output"))
    )
    (net (code "108") (name "unconnected-(AND-NC-Pad11)") (class "Default")
      (node (ref "AND") (pin "11") (pinfunction "NC_11") (pintype "no_connect"))
    )
    (net (code "109") (name "unconnected-(AND-NC_2-Pad3)") (class "Default")
      (node (ref "AND") (pin "3") (pinfunction "NC_2_3") (pintype "no_connect"))
    )
    (net (code "110") (name "unconnected-(IC1-CLKOUT{slash}SOF-Pad3)") (class "Default")
      (node (ref "IC1") (pin "3") (pinfunction "CLKOUT/SOF_3") (pintype "output"))
    )
    (net (code "111") (name "unconnected-(IC1-~{INT}-Pad12)") (class "Default")
      (node (ref "IC1") (pin "12") (pinfunction "~{INT}_12") (pintype "output"))
    )
    (net (code "112") (name "unconnected-(IC1-~{RX0BF}-Pad11)") (class "Default")
      (node (ref "IC1") (pin "11") (pinfunction "~{RX0BF}_11") (pintype "output"))
    )
    (net (code "113") (name "unconnected-(IC1-~{RX1BF}-Pad10)") (class "Default")
      (node (ref "IC1") (pin "10") (pinfunction "~{RX1BF}_10") (pintype "output"))
    )
    (net (code "114") (name "unconnected-(IC1-~{TX0RTS}-Pad4)") (class "Default")
      (node (ref "IC1") (pin "4") (pinfunction "~{TX0RTS}_4") (pintype "input"))
    )
    (net (code "115") (name "unconnected-(IC1-~{TX1RTS}-Pad5)") (class "Default")
      (node (ref "IC1") (pin "5") (pinfunction "~{TX1RTS}_5") (pintype "input"))
    )
    (net (code "116") (name "unconnected-(IC1-~{TX2RTS}-Pad6)") (class "Default")
      (node (ref "IC1") (pin "6") (pinfunction "~{TX2RTS}_6") (pintype "input"))
    )
    (net (code "117") (name "unconnected-(IC2-VREF-Pad5)") (class "Default")
      (node (ref "IC2") (pin "5") (pinfunction "VREF_5") (pintype "output"))
    )
    (net (code "118") (name "unconnected-(IC3-CLKOUT{slash}SOF-Pad3)") (class "Default")
      (node (ref "IC3") (pin "3") (pinfunction "CLKOUT/SOF_3") (pintype "output"))
    )
    (net (code "119") (name "unconnected-(IC3-~{INT}-Pad12)") (class "Default")
      (node (ref "IC3") (pin "12") (pinfunction "~{INT}_12") (pintype "output"))
    )
    (net (code "120") (name "unconnected-(IC3-~{RX0BF}-Pad11)") (class "Default")
      (node (ref "IC3") (pin "11") (pinfunction "~{RX0BF}_11") (pintype "output"))
    )
    (net (code "121") (name "unconnected-(IC3-~{RX1BF}-Pad10)") (class "Default")
      (node (ref "IC3") (pin "10") (pinfunction "~{RX1BF}_10") (pintype "output"))
    )
    (net (code "122") (name "unconnected-(IC3-~{TX0RTS}-Pad4)") (class "Default")
      (node (ref "IC3") (pin "4") (pinfunction "~{TX0RTS}_4") (pintype "input"))
    )
    (net (code "123") (name "unconnected-(IC3-~{TX1RTS}-Pad5)") (class "Default")
      (node (ref "IC3") (pin "5") (pinfunction "~{TX1RTS}_5") (pintype "input"))
    )
    (net (code "124") (name "unconnected-(IC3-~{TX2RTS}-Pad6)") (class "Default")
      (node (ref "IC3") (pin "6") (pinfunction "~{TX2RTS}_6") (pintype "input"))
    )
    (net (code "125") (name "unconnected-(IC4-VREF-Pad5)") (class "Default")
      (node (ref "IC4") (pin "5") (pinfunction "VREF_5") (pintype "output"))
    )
    (net (code "126") (name "unconnected-(IC5-GND-Pad2)") (class "Default")
      (node (ref "IC5") (pin "2") (pinfunction "GND_2") (pintype "bidirectional"))
    )
    (net (code "127") (name "unconnected-(M2-D3-PadJ7.7)") (class "Default")
      (node (ref "M2") (pin "J7.7") (pinfunction "D3_J7.7") (pintype "bidirectional"))
    )
    (net (code "128") (name "unconnected-(Q1-S_3-Pad3)") (class "Default")
      (node (ref "Q1") (pin "3") (pinfunction "S_3_3") (pintype "bidirectional"))
    )
    (net (code "129") (name "unconnected-(XOR-2A-Pad4)") (class "Default")
      (node (ref "XOR") (pin "4") (pinfunction "2A_4") (pintype "input"))
    )
    (net (code "130") (name "unconnected-(XOR-2B-Pad5)") (class "Default")
      (node (ref "XOR") (pin "5") (pinfunction "2B_5") (pintype "input"))
    )
    (net (code "131") (name "unconnected-(XOR-2Y-Pad6)") (class "Default")
      (node (ref "XOR") (pin "6") (pinfunction "2Y_6") (pintype "output"))
    )
    (net (code "132") (name "unconnected-(XOR-3A-Pad9)") (class "Default")
      (node (ref "XOR") (pin "9") (pinfunction "3A_9") (pintype "input"))
    )
    (net (code "133") (name "unconnected-(XOR-3B-Pad10)") (class "Default")
      (node (ref "XOR") (pin "10") (pinfunction "3B_10") (pintype "input"))
    )
    (net (code "134") (name "unconnected-(XOR-3Y-Pad8)") (class "Default")
      (node (ref "XOR") (pin "8") (pinfunction "3Y_8") (pintype "output"))
    )
    (net (code "135") (name "unconnected-(XOR-4A-Pad12)") (class "Default")
      (node (ref "XOR") (pin "12") (pinfunction "4A_12") (pintype "input"))
    )
    (net (code "136") (name "unconnected-(XOR-4B-Pad13)") (class "Default")
      (node (ref "XOR") (pin "13") (pinfunction "4B_13") (pintype "input"))
    )
    (net (code "137") (name "unconnected-(XOR-4Y-Pad11)") (class "Default")
      (node (ref "XOR") (pin "11") (pinfunction "4Y_11") (pintype "output"))
    )
  )
)
